# tie-il0.net
KiCad netlist of a schematic drawn in Altium Designer
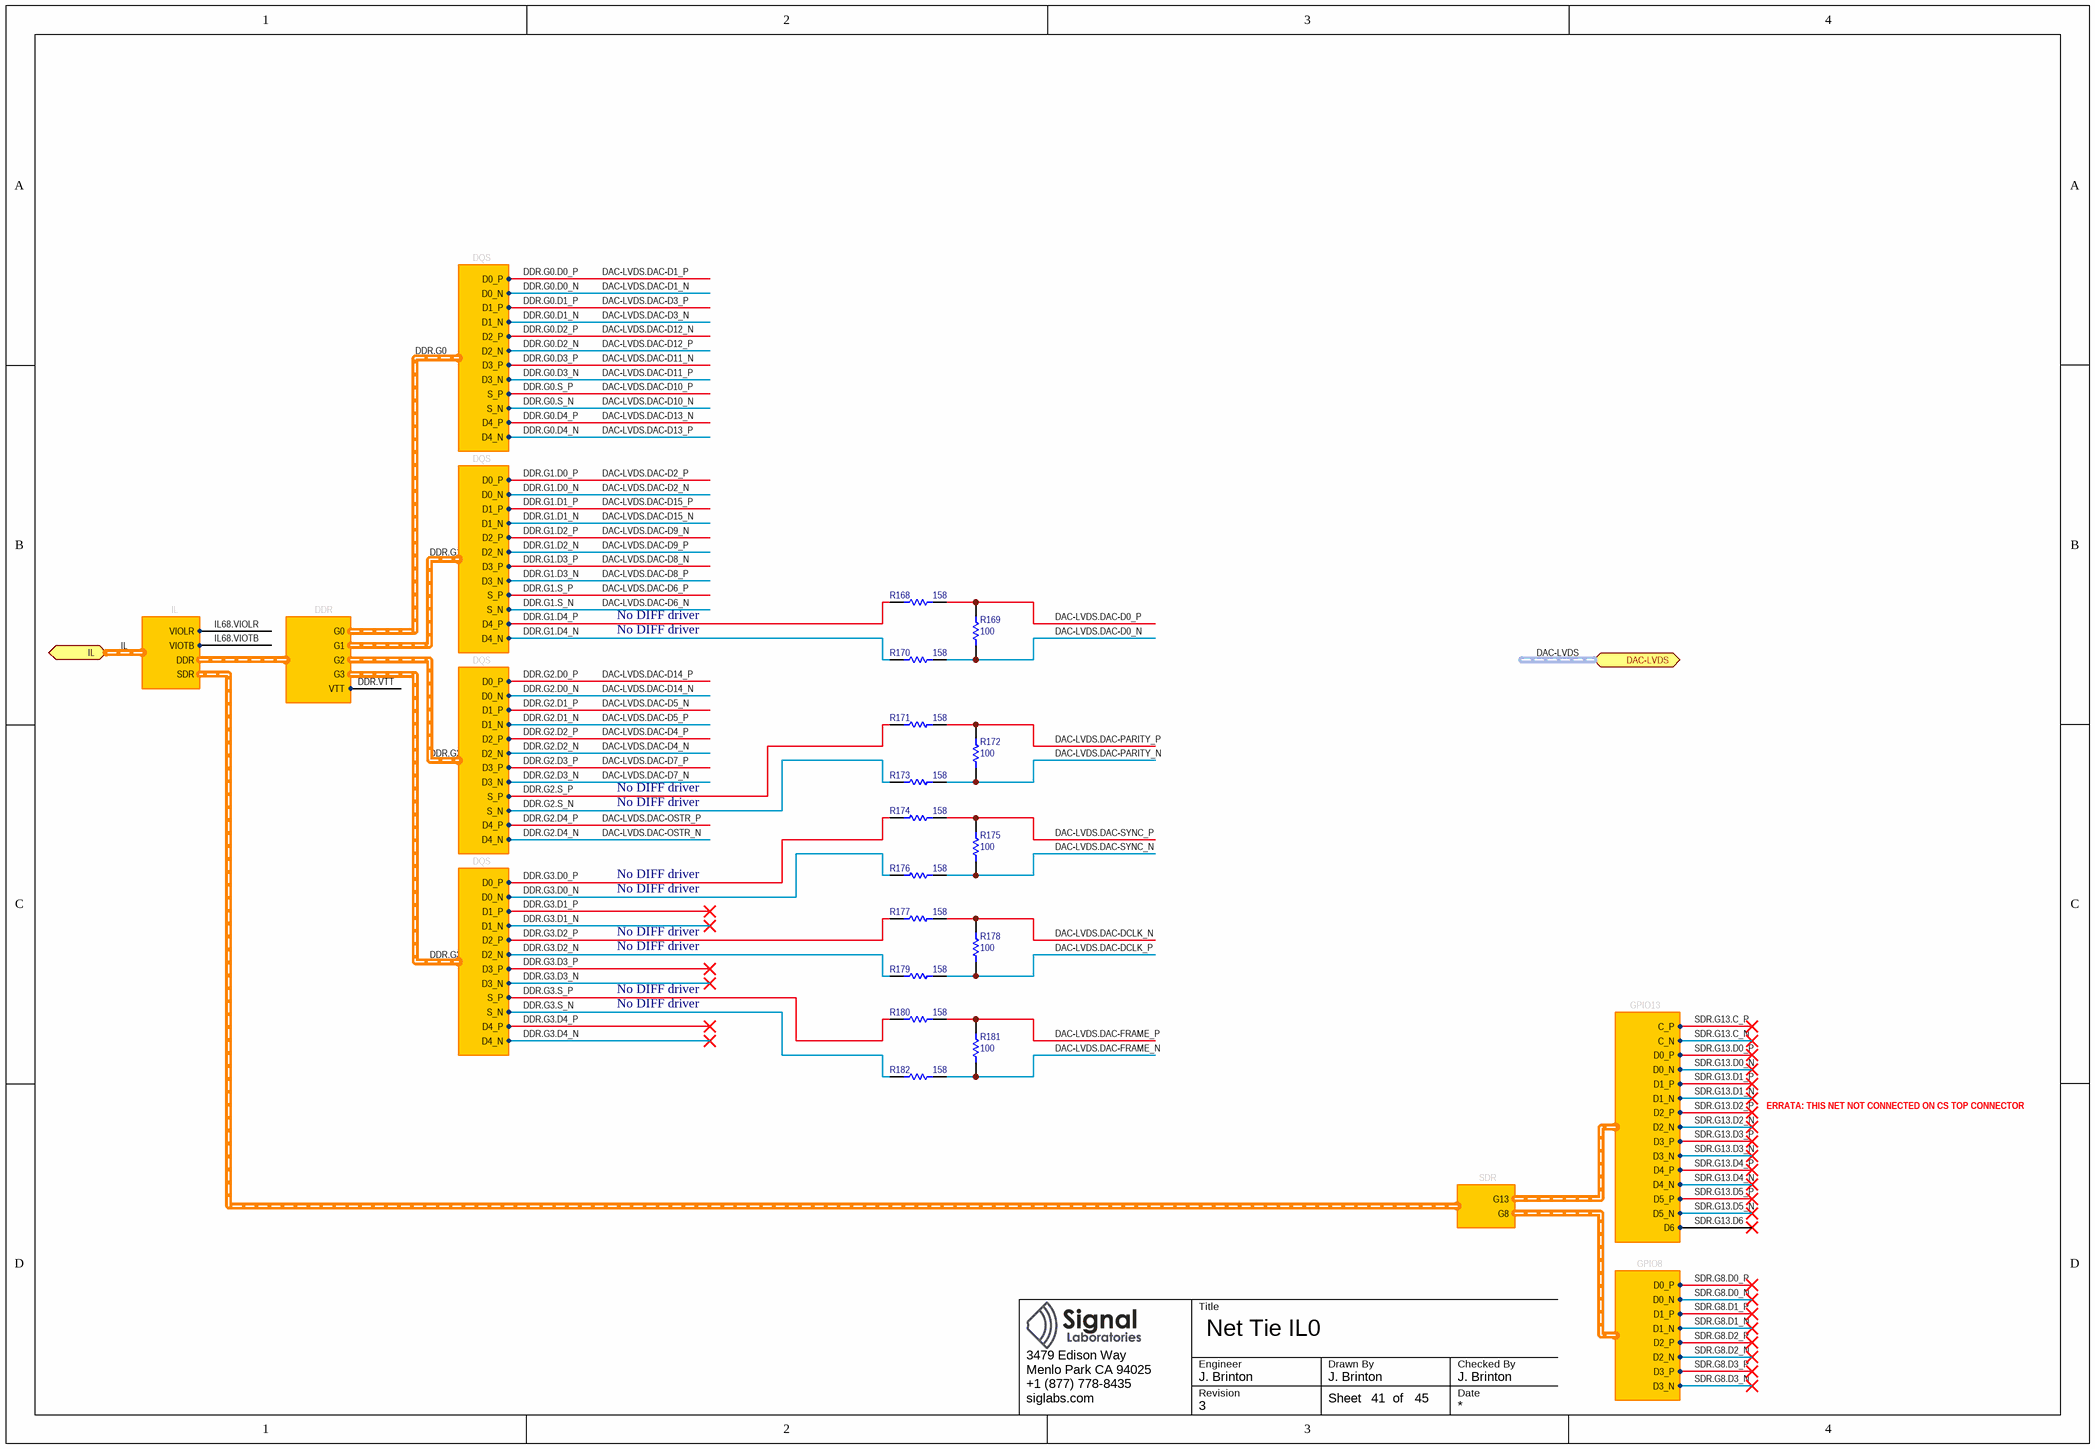
[diagram p0: tie-il0.SchDoc]

(export (version "E")
  (design (tool "Eeschema 10.0.6"))
  (components
    (comp (ref "R168")
      (value "158")
      (footprint "RESC1005X40N")
      (description "Thick Film 158 ±1% 0402")
      (fields (field (name "MANUFACTURER") "Panasonic") (field (name "TOLERANCE") "±1%"))
      (libsource (lib "Graviton") (part "RES 0402"))
    )
    (comp (ref "R169")
      (value "100")
      (footprint "RESC1005X40N")
      (description "Thick Film 100 ±1% 0402")
      (fields (field (name "MANUFACTURER") "Panasonic") (field (name "TOLERANCE") "±1%"))
      (libsource (lib "Graviton") (part "RES 0402"))
    )
    (comp (ref "R170")
      (value "158")
      (footprint "RESC1005X40N")
      (description "Thick Film 158 ±1% 0402")
      (fields (field (name "MANUFACTURER") "Panasonic") (field (name "TOLERANCE") "±1%"))
      (libsource (lib "Graviton") (part "RES 0402"))
    )
    (comp (ref "R171")
      (value "158")
      (footprint "RESC1005X40N")
      (description "Thick Film 158 ±1% 0402")
      (fields (field (name "MANUFACTURER") "Panasonic") (field (name "TOLERANCE") "±1%"))
      (libsource (lib "Graviton") (part "RES 0402"))
    )
    (comp (ref "R172")
      (value "100")
      (footprint "RESC1005X40N")
      (description "Thick Film 100 ±1% 0402")
      (fields (field (name "MANUFACTURER") "Panasonic") (field (name "TOLERANCE") "±1%"))
      (libsource (lib "Graviton") (part "RES 0402"))
    )
    (comp (ref "R173")
      (value "158")
      (footprint "RESC1005X40N")
      (description "Thick Film 158 ±1% 0402")
      (fields (field (name "MANUFACTURER") "Panasonic") (field (name "TOLERANCE") "±1%"))
      (libsource (lib "Graviton") (part "RES 0402"))
    )
    (comp (ref "R174")
      (value "158")
      (footprint "RESC1005X40N")
      (description "Thick Film 158 ±1% 0402")
      (fields (field (name "MANUFACTURER") "Panasonic") (field (name "TOLERANCE") "±1%"))
      (libsource (lib "Graviton") (part "RES 0402"))
    )
    (comp (ref "R175")
      (value "100")
      (footprint "RESC1005X40N")
      (description "Thick Film 100 ±1% 0402")
      (fields (field (name "MANUFACTURER") "Panasonic") (field (name "TOLERANCE") "±1%"))
      (libsource (lib "Graviton") (part "RES 0402"))
    )
    (comp (ref "R176")
      (value "158")
      (footprint "RESC1005X40N")
      (description "Thick Film 158 ±1% 0402")
      (fields (field (name "MANUFACTURER") "Panasonic") (field (name "TOLERANCE") "±1%"))
      (libsource (lib "Graviton") (part "RES 0402"))
    )
    (comp (ref "R177")
      (value "158")
      (footprint "RESC1005X40N")
      (description "Thick Film 158 ±1% 0402")
      (fields (field (name "MANUFACTURER") "Panasonic") (field (name "TOLERANCE") "±1%"))
      (libsource (lib "Graviton") (part "RES 0402"))
    )
    (comp (ref "R178")
      (value "100")
      (footprint "RESC1005X40N")
      (description "Thick Film 100 ±1% 0402")
      (fields (field (name "MANUFACTURER") "Panasonic") (field (name "TOLERANCE") "±1%"))
      (libsource (lib "Graviton") (part "RES 0402"))
    )
    (comp (ref "R179")
      (value "158")
      (footprint "RESC1005X40N")
      (description "Thick Film 158 ±1% 0402")
      (fields (field (name "MANUFACTURER") "Panasonic") (field (name "TOLERANCE") "±1%"))
      (libsource (lib "Graviton") (part "RES 0402"))
    )
    (comp (ref "R180")
      (value "158")
      (footprint "RESC1005X40N")
      (description "Thick Film 158 ±1% 0402")
      (fields (field (name "MANUFACTURER") "Panasonic") (field (name "TOLERANCE") "±1%"))
      (libsource (lib "Graviton") (part "RES 0402"))
    )
    (comp (ref "R181")
      (value "100")
      (footprint "RESC1005X40N")
      (description "Thick Film 100 ±1% 0402")
      (fields (field (name "MANUFACTURER") "Panasonic") (field (name "TOLERANCE") "±1%"))
      (libsource (lib "Graviton") (part "RES 0402"))
    )
    (comp (ref "R182")
      (value "158")
      (footprint "RESC1005X40N")
      (description "Thick Film 158 ±1% 0402")
      (fields (field (name "MANUFACTURER") "Panasonic") (field (name "TOLERANCE") "±1%"))
      (libsource (lib "Graviton") (part "RES 0402"))
    )
  )
  (nets
    (net (code "8") (name "/DAC-LVDS.DAC-D0_N") (class "Default")
      (node (ref "R169") (pin "2") (pinfunction "2_2") (pintype "passive"))
      (node (ref "R170") (pin "1") (pinfunction "1_1") (pintype "passive"))
    )
    (net (code "9") (name "/DAC-LVDS.DAC-D0_P") (class "Default")
      (node (ref "R168") (pin "1") (pinfunction "1_1") (pintype "passive"))
      (node (ref "R169") (pin "1") (pinfunction "1_1") (pintype "passive"))
    )
    (net (code "40") (name "/DAC-LVDS.DAC-DCLK_N") (class "Default")
      (node (ref "R177") (pin "1") (pinfunction "1_1") (pintype "passive"))
      (node (ref "R178") (pin "1") (pinfunction "1_1") (pintype "passive"))
    )
    (net (code "41") (name "/DAC-LVDS.DAC-DCLK_P") (class "Default")
      (node (ref "R178") (pin "2") (pinfunction "2_2") (pintype "passive"))
      (node (ref "R179") (pin "1") (pinfunction "1_1") (pintype "passive"))
    )
    (net (code "42") (name "/DAC-LVDS.DAC-FRAME_N") (class "Default")
      (node (ref "R181") (pin "2") (pinfunction "2_2") (pintype "passive"))
      (node (ref "R182") (pin "1") (pinfunction "1_1") (pintype "passive"))
    )
    (net (code "43") (name "/DAC-LVDS.DAC-FRAME_P") (class "Default")
      (node (ref "R180") (pin "1") (pinfunction "1_1") (pintype "passive"))
      (node (ref "R181") (pin "1") (pinfunction "1_1") (pintype "passive"))
    )
    (net (code "46") (name "/DAC-LVDS.DAC-PARITY_N") (class "Default")
      (node (ref "R172") (pin "2") (pinfunction "2_2") (pintype "passive"))
      (node (ref "R173") (pin "1") (pinfunction "1_1") (pintype "passive"))
    )
    (net (code "47") (name "/DAC-LVDS.DAC-PARITY_P") (class "Default")
      (node (ref "R171") (pin "1") (pinfunction "1_1") (pintype "passive"))
      (node (ref "R172") (pin "1") (pinfunction "1_1") (pintype "passive"))
    )
    (net (code "48") (name "/DAC-LVDS.DAC-SYNC_N") (class "Default")
      (node (ref "R175") (pin "2") (pinfunction "2_2") (pintype "passive"))
      (node (ref "R176") (pin "1") (pinfunction "1_1") (pintype "passive"))
    )
    (net (code "49") (name "/DAC-LVDS.DAC-SYNC_P") (class "Default")
      (node (ref "R174") (pin "1") (pinfunction "1_1") (pintype "passive"))
      (node (ref "R175") (pin "1") (pinfunction "1_1") (pintype "passive"))
    )
    (net (code "51") (name "/DDR.G1.D4_N") (class "Default")
      (node (ref "R170") (pin "2") (pinfunction "2_2") (pintype "passive"))
    )
    (net (code "52") (name "/DDR.G1.D4_P") (class "Default")
      (node (ref "R168") (pin "2") (pinfunction "2_2") (pintype "passive"))
    )
    (net (code "54") (name "/DDR.G2.S_N") (class "Default")
      (node (ref "R173") (pin "2") (pinfunction "2_2") (pintype "passive"))
    )
    (net (code "55") (name "/DDR.G2.S_P") (class "Default")
      (node (ref "R171") (pin "2") (pinfunction "2_2") (pintype "passive"))
    )
    (net (code "57") (name "/DDR.G3.D0_N") (class "Default")
      (node (ref "R176") (pin "2") (pinfunction "2_2") (pintype "passive"))
    )
    (net (code "58") (name "/DDR.G3.D0_P") (class "Default")
      (node (ref "R174") (pin "2") (pinfunction "2_2") (pintype "passive"))
    )
    (net (code "61") (name "/DDR.G3.D2_N") (class "Default")
      (node (ref "R179") (pin "2") (pinfunction "2_2") (pintype "passive"))
    )
    (net (code "62") (name "/DDR.G3.D2_P") (class "Default")
      (node (ref "R177") (pin "2") (pinfunction "2_2") (pintype "passive"))
    )
    (net (code "67") (name "/DDR.G3.S_N") (class "Default")
      (node (ref "R182") (pin "2") (pinfunction "2_2") (pintype "passive"))
    )
    (net (code "68") (name "/DDR.G3.S_P") (class "Default")
      (node (ref "R180") (pin "2") (pinfunction "2_2") (pintype "passive"))
    )
  )
)
